# v1.net
KiCad netlist of a schematic drawn in EAGLE
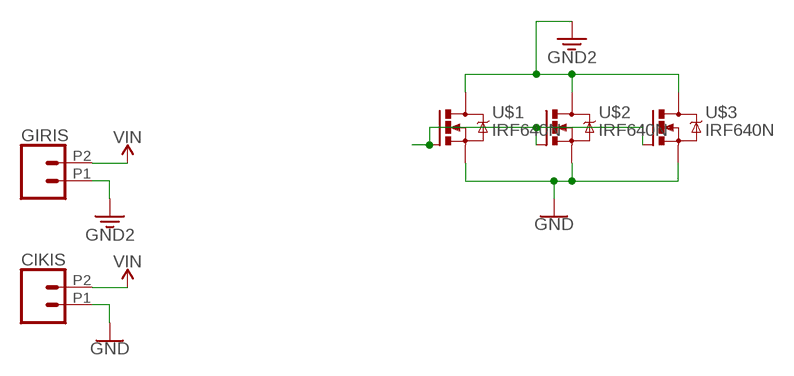
[diagram p0: schematic, sheet 1]

(export (version "E")
  (design (tool "Eeschema 10.0.6"))
  (components
    (comp (ref "CIKIS")
      (value "CONN_022.54MM_SCREWTERM")
      (footprint "eagle-import:1X02_2.54_SCREWTERM")
      (libsource (lib "eagle-import") (part "CONN_022.54MM_SCREWTERM"))
    )
    (comp (ref "GIRIS")
      (value "CONN_022.54MM_SCREWTERM")
      (footprint "eagle-import:1X02_2.54_SCREWTERM")
      (libsource (lib "eagle-import") (part "CONN_022.54MM_SCREWTERM"))
    )
    (comp (ref "U$1")
      (value "IRF640N")
      (footprint "eagle-import:TO-220-PAD")
      (libsource (lib "eagle-import") (part "IRF640N"))
    )
    (comp (ref "U$2")
      (value "IRF640N")
      (footprint "eagle-import:TO-220-PAD")
      (libsource (lib "eagle-import") (part "IRF640N"))
    )
    (comp (ref "U$3")
      (value "IRF640N")
      (footprint "eagle-import:TO-220-PAD")
      (libsource (lib "eagle-import") (part "IRF640N"))
    )
  )
  (nets
    (net (code "1") (name "GND") (class "Default")
      (node (ref "CIKIS") (pin "P1") (pinfunction "1_P1") (pintype "passive"))
      (node (ref "U$1") (pin "3") (pinfunction "S_3") (pintype "passive"))
      (node (ref "U$2") (pin "3") (pinfunction "S_3") (pintype "passive"))
      (node (ref "U$3") (pin "3") (pinfunction "S_3") (pintype "passive"))
    )
    (net (code "2") (name "GND2") (class "Default")
      (node (ref "GIRIS") (pin "P1") (pinfunction "1_P1") (pintype "passive"))
      (node (ref "U$1") (pin "TAB") (pinfunction "D_TAB") (pintype "passive"))
      (node (ref "U$2") (pin "TAB") (pinfunction "D_TAB") (pintype "passive"))
      (node (ref "U$3") (pin "TAB") (pinfunction "D_TAB") (pintype "passive"))
    )
    (net (code "3") (name "Net-(U$1-G)") (class "Default")
      (node (ref "U$1") (pin "1") (pinfunction "G_1") (pintype "passive"))
      (node (ref "U$2") (pin "1") (pinfunction "G_1") (pintype "passive"))
      (node (ref "U$3") (pin "1") (pinfunction "G_1") (pintype "passive"))
    )
    (net (code "4") (name "VIN") (class "Default")
      (node (ref "CIKIS") (pin "P2") (pinfunction "2_P2") (pintype "passive"))
      (node (ref "GIRIS") (pin "P2") (pinfunction "2_P2") (pintype "passive"))
    )
  )
)
